# USB.net
KiCad netlist of a schematic drawn in Altium Designer
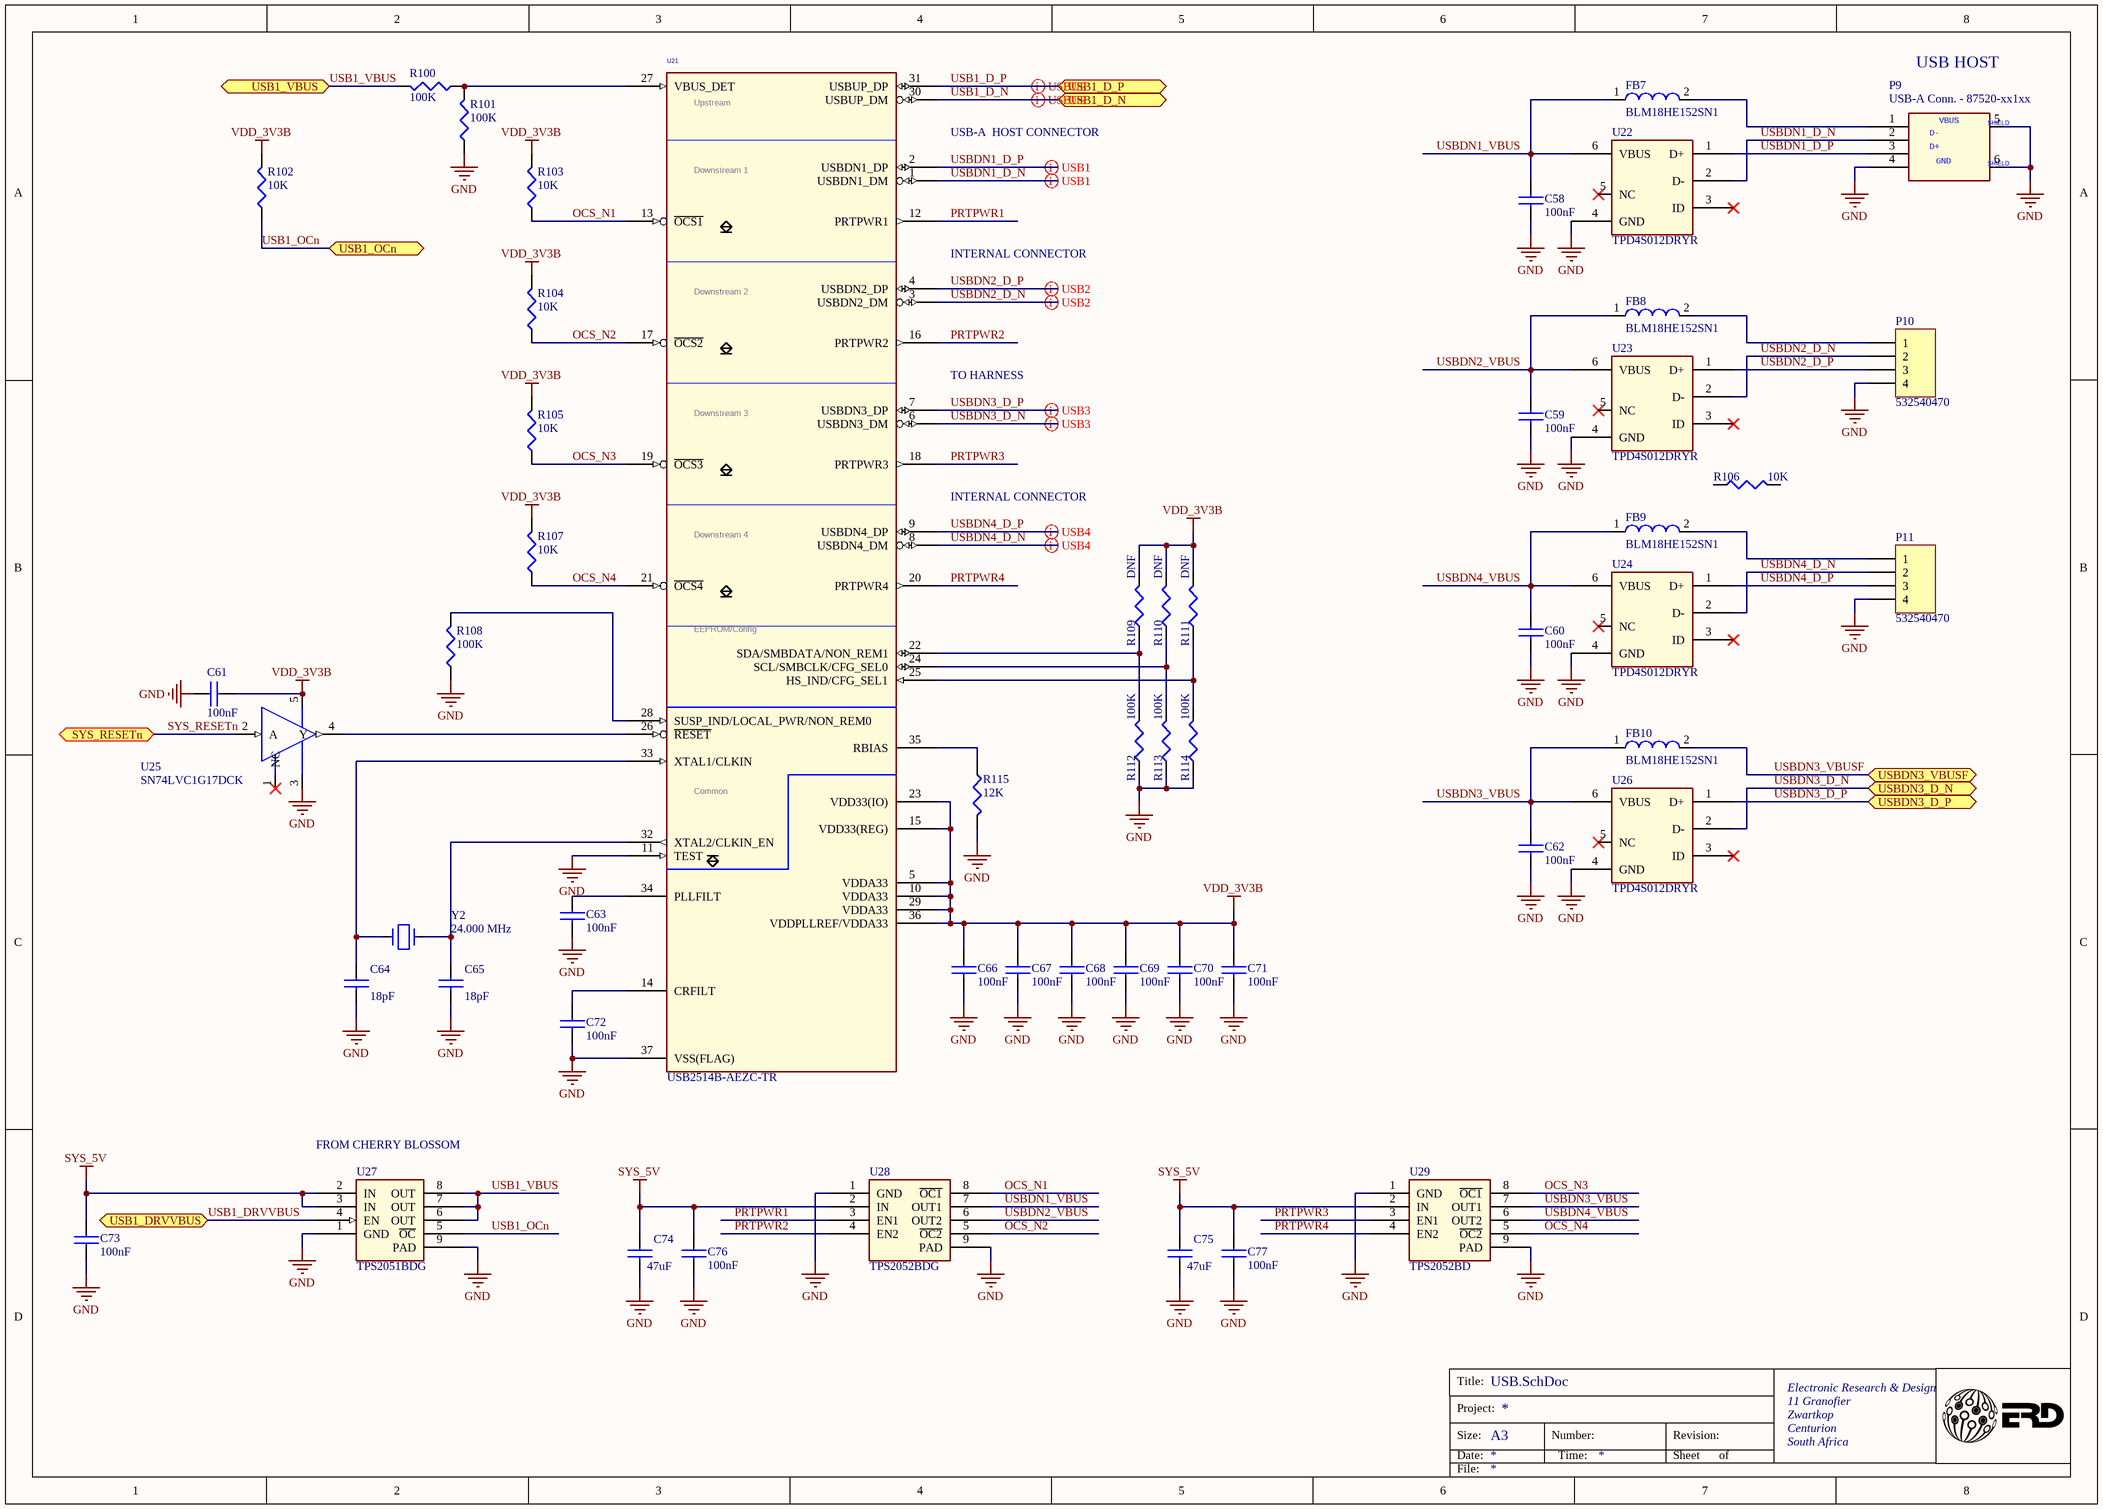
[diagram p0: USB.SchDoc]

(export (version "E")
  (design (tool "Eeschema 10.0.6"))
  (components
    (comp (ref "C58")
      (value "100nF")
      (footprint "CC0402")
      (description "CAP CER 0.1UF 50V 10% X7R 0402")
      (fields (field (name "MANUFACTURER") "Murata") (field (name "PARTNUMBER") "GCM155R71H104KE02D"))
      (libsource (lib "ERD TiAm") (part "CAP CER 0.1UF 10V 10% X5R 0402"))
    )
    (comp (ref "C59")
      (value "100nF")
      (footprint "CC0402")
      (description "CAP CER 0.1UF 50V 10% X7R 0402")
      (fields (field (name "MANUFACTURER") "Murata") (field (name "PARTNUMBER") "GCM155R71H104KE02D"))
      (libsource (lib "ERD TiAm") (part "CAP CER 0.1UF 10V 10% X5R 0402"))
    )
    (comp (ref "C60")
      (value "100nF")
      (footprint "CC0402")
      (description "CAP CER 0.1UF 50V 10% X7R 0402")
      (fields (field (name "MANUFACTURER") "Murata") (field (name "PARTNUMBER") "GCM155R71H104KE02D"))
      (libsource (lib "ERD TiAm") (part "CAP CER 0.1UF 10V 10% X5R 0402"))
    )
    (comp (ref "C61")
      (value "100nF")
      (footprint "CC0402")
      (description "CAP CER 0.1UF 50V 10% X7R 0402")
      (fields (field (name "MANUFACTURER") "Murata") (field (name "PARTNUMBER") "GCM155R71H104KE02D"))
      (libsource (lib "ERD TiAm") (part "CAP CER 0.1UF 10V 10% X5R 0402"))
    )
    (comp (ref "C62")
      (value "100nF")
      (footprint "CC0402")
      (description "CAP CER 0.1UF 50V 10% X7R 0402")
      (fields (field (name "MANUFACTURER") "Murata") (field (name "PARTNUMBER") "GCM155R71H104KE02D"))
      (libsource (lib "ERD TiAm") (part "CAP CER 0.1UF 10V 10% X5R 0402"))
    )
    (comp (ref "C63")
      (value "100nF")
      (footprint "CC0402")
      (description "CAP CER 0.1UF 50V 10% X7R 0402")
      (fields (field (name "MANUFACTURER") "Murata") (field (name "PARTNUMBER") "GCM155R71H104KE02D"))
      (libsource (lib "ERD TiAm") (part "CAP CER 0.1UF 10V 10% X5R 0402"))
    )
    (comp (ref "C64")
      (value "18pF")
      (footprint "CC0402")
      (description "CAP CER 18pF 50V 5% C0G 0402")
      (fields (field (name "MANUFACTURER") "AVX") (field (name "PARTNUMBER") "GJM1555C1H180FB01D"))
      (libsource (lib "ERD TiAm") (part "CAP CER 2.2UF 6.3V 10% X5R 0402"))
    )
    (comp (ref "C65")
      (value "18pF")
      (footprint "CC0402")
      (description "CAP CER 18pF 50V 5% C0G 0402")
      (fields (field (name "MANUFACTURER") "AVX") (field (name "PARTNUMBER") "GJM1555C1H180FB01D"))
      (libsource (lib "ERD TiAm") (part "CAP CER 2.2UF 6.3V 10% X5R 0402"))
    )
    (comp (ref "C66")
      (value "100nF")
      (footprint "CC0402")
      (description "CAP CER 0.1UF 50V 10% X7R 0402")
      (fields (field (name "MANUFACTURER") "Murata") (field (name "PARTNUMBER") "GCM155R71H104KE02D"))
      (libsource (lib "ERD TiAm") (part "CAP CER 0.1UF 10V 10% X5R 0402"))
    )
    (comp (ref "C67")
      (value "100nF")
      (footprint "CC0402")
      (description "CAP CER 0.1UF 50V 10% X7R 0402")
      (fields (field (name "MANUFACTURER") "Murata") (field (name "PARTNUMBER") "GCM155R71H104KE02D"))
      (libsource (lib "ERD TiAm") (part "CAP CER 0.1UF 10V 10% X5R 0402"))
    )
    (comp (ref "C68")
      (value "100nF")
      (footprint "CC0402")
      (description "CAP CER 0.1UF 50V 10% X7R 0402")
      (fields (field (name "MANUFACTURER") "Murata") (field (name "PARTNUMBER") "GCM155R71H104KE02D"))
      (libsource (lib "ERD TiAm") (part "CAP CER 0.1UF 10V 10% X5R 0402"))
    )
    (comp (ref "C69")
      (value "100nF")
      (footprint "CC0402")
      (description "CAP CER 0.1UF 50V 10% X7R 0402")
      (fields (field (name "MANUFACTURER") "Murata") (field (name "PARTNUMBER") "GCM155R71H104KE02D"))
      (libsource (lib "ERD TiAm") (part "CAP CER 0.1UF 10V 10% X5R 0402"))
    )
    (comp (ref "C70")
      (value "100nF")
      (footprint "CC0402")
      (description "CAP CER 0.1UF 50V 10% X7R 0402")
      (fields (field (name "MANUFACTURER") "Murata") (field (name "PARTNUMBER") "GCM155R71H104KE02D"))
      (libsource (lib "ERD TiAm") (part "CAP CER 0.1UF 10V 10% X5R 0402"))
    )
    (comp (ref "C71")
      (value "100nF")
      (footprint "CC0402")
      (description "CAP CER 0.1UF 50V 10% X7R 0402")
      (fields (field (name "MANUFACTURER") "Murata") (field (name "PARTNUMBER") "GCM155R71H104KE02D"))
      (libsource (lib "ERD TiAm") (part "CAP CER 0.1UF 10V 10% X5R 0402"))
    )
    (comp (ref "C72")
      (value "100nF")
      (footprint "CC0402")
      (description "CAP CER 0.1UF 50V 10% X7R 0402")
      (fields (field (name "MANUFACTURER") "Murata") (field (name "PARTNUMBER") "GCM155R71H104KE02D"))
      (libsource (lib "ERD TiAm") (part "CAP CER 0.1UF 10V 10% X5R 0402"))
    )
    (comp (ref "C73")
      (value "100nF")
      (footprint "CC0402")
      (description "CAP CER 0.1UF 50V 10% X7R 0402")
      (fields (field (name "MANUFACTURER") "Murata") (field (name "PARTNUMBER") "GCM155R71H104KE02D"))
      (libsource (lib "ERD TiAm") (part "CAP CER 0.1UF 10V 10% X5R 0402"))
    )
    (comp (ref "C74")
      (value "47uF")
      (footprint "RC1206")
      (description "CAP CER 47UF 25V 20% X5R 1206")
      (fields (field (name "MANUFACTURER") "Murata") (field (name "PART NUMBER") "C3216X5R1E476M160AC"))
      (libsource (lib "ERD TiAm") (part "CAP CER 0.1UF 10V 10% X5R 0402"))
    )
    (comp (ref "C75")
      (value "47uF")
      (footprint "RC1206")
      (description "CAP CER 47UF 25V 20% X5R 1206")
      (fields (field (name "MANUFACTURER") "Murata") (field (name "PART NUMBER") "C3216X5R1E476M160AC"))
      (libsource (lib "ERD TiAm") (part "CAP CER 0.1UF 10V 10% X5R 0402"))
    )
    (comp (ref "C76")
      (value "100nF")
      (footprint "CC0402")
      (description "CAP CER 0.1UF 50V 10% X7R 0402")
      (fields (field (name "MANUFACTURER") "Murata") (field (name "PARTNUMBER") "GCM155R71H104KE02D"))
      (libsource (lib "ERD TiAm") (part "CAP CER 0.1UF 10V 10% X5R 0402"))
    )
    (comp (ref "C77")
      (value "100nF")
      (footprint "CC0402")
      (description "CAP CER 0.1UF 50V 10% X7R 0402")
      (fields (field (name "MANUFACTURER") "Murata") (field (name "PARTNUMBER") "GCM155R71H104KE02D"))
      (libsource (lib "ERD TiAm") (part "CAP CER 0.1UF 10V 10% X5R 0402"))
    )
    (comp (ref "FB7")
      (value "BLM18HE152SN1")
      (footprint "LC0603")
      (description "FERRITE, 500mA, 500mOHM, 0603")
      (libsource (lib "BEAGLEBONEBLACK_REV A5B") (part "FER_180_200_0"))
    )
    (comp (ref "FB8")
      (value "BLM18HE152SN1")
      (footprint "LC0603")
      (description "FERRITE, 500mA, 500mOHM, 0603")
      (libsource (lib "BEAGLEBONEBLACK_REV A5B") (part "FER_180_200_0"))
    )
    (comp (ref "FB9")
      (value "BLM18HE152SN1")
      (footprint "LC0603")
      (description "FERRITE, 500mA, 500mOHM, 0603")
      (libsource (lib "BEAGLEBONEBLACK_REV A5B") (part "FER_180_200_0"))
    )
    (comp (ref "FB10")
      (value "BLM18HE152SN1")
      (footprint "LC0603")
      (description "FERRITE, 500mA, 500mOHM, 0603")
      (libsource (lib "BEAGLEBONEBLACK_REV A5B") (part "FER_180_200_0"))
    )
    (comp (ref "P9")
      (value "USB-A Conn. - 87520-xx1xx")
      (description "CONN RCPT USB TYPE A R/A PCB")
      (fields (field (name "MANUFACTURER") "FCI") (field (name "MANUFACTURER PART NUMBER") "87520-0010BLF"))
      (libsource (lib "BEAGLEBONEBLACK_REV A5B") (part "CONN_54819-0578_2"))
    )
    (comp (ref "P10")
      (value "532540470")
      (footprint "HDR1X4")
      (description "Header, RA, 4-circuit, 2mm pitch, TH")
      (fields (field (name "MANUFACTURER") "Molex"))
      (libsource (lib "Miscellaneous Connectors") (part "Header 4"))
    )
    (comp (ref "P11")
      (value "532540470")
      (footprint "HDR1X4")
      (description "Header, RA, 4-circuit, 2mm pitch, TH")
      (fields (field (name "MANUFACTURER") "Molex"))
      (libsource (lib "Miscellaneous Connectors") (part "Header 4"))
    )
    (comp (ref "R100")
      (value "100K")
      (footprint "RC0402")
      (description "RES, 100K OHM, 1/16W, 1%, 0402")
      (fields (field (name "MANUFACTURER") "Yageo") (field (name "PART NUMBER") "RC0402FR-07100KL"))
      (libsource (lib "ERD TiAm") (part "RES_10K_1/16W_1%_0402"))
    )
    (comp (ref "R101")
      (value "100K")
      (footprint "RC0402")
      (description "RES, 100K OHM, 1/16W, 1%, 0402")
      (fields (field (name "MANUFACTURER") "Yageo") (field (name "PART NUMBER") "RC0402FR-07100KL"))
      (libsource (lib "ERD TiAm") (part "RES_10K_1/16W_1%_0402"))
    )
    (comp (ref "R102")
      (value "10K")
      (footprint "RC0402")
      (description "RES, 10K OHM, 1/16W, 1%, 0402")
      (fields (field (name "MANUFACTURER") "Yageo") (field (name "PART NUMBER") "RC0402FR-0710KL"))
      (libsource (lib "ERD TiAm") (part "RES_10K_1/16W_1%_0402"))
    )
    (comp (ref "R103")
      (value "10K")
      (footprint "RC0402")
      (description "RES, 10K OHM, 1/16W, 1%, 0402")
      (fields (field (name "MANUFACTURER") "Yageo") (field (name "PART NUMBER") "RC0402FR-0710KL"))
      (libsource (lib "ERD TiAm") (part "RES_10K_1/16W_1%_0402"))
    )
    (comp (ref "R104")
      (value "10K")
      (footprint "RC0402")
      (description "RES, 10K OHM, 1/16W, 1%, 0402")
      (fields (field (name "MANUFACTURER") "Yageo") (field (name "PART NUMBER") "RC0402FR-0710KL"))
      (libsource (lib "ERD TiAm") (part "RES_10K_1/16W_1%_0402"))
    )
    (comp (ref "R105")
      (value "10K")
      (footprint "RC0402")
      (description "RES, 10K OHM, 1/16W, 1%, 0402")
      (fields (field (name "MANUFACTURER") "Yageo") (field (name "PART NUMBER") "RC0402FR-0710KL"))
      (libsource (lib "ERD TiAm") (part "RES_10K_1/16W_1%_0402"))
    )
    (comp (ref "R106")
      (value "10K")
      (footprint "RC0402")
      (description "RES, 10K OHM, 1/16W, 1%, 0402")
      (fields (field (name "MANUFACTURER") "Yageo") (field (name "PART NUMBER") "RC0402FR-0710KL"))
      (libsource (lib "ERD TiAm") (part "RES_10K_1/16W_1%_0402"))
    )
    (comp (ref "R107")
      (value "10K")
      (footprint "RC0402")
      (description "RES, 10K OHM, 1/16W, 1%, 0402")
      (fields (field (name "MANUFACTURER") "Yageo") (field (name "PART NUMBER") "RC0402FR-0710KL"))
      (libsource (lib "ERD TiAm") (part "RES_10K_1/16W_1%_0402"))
    )
    (comp (ref "R108")
      (value "100K")
      (footprint "RC0402")
      (description "RES, 100K OHM, 1/16W, 1%, 0402")
      (fields (field (name "MANUFACTURER") "Yageo") (field (name "PART NUMBER") "RC0402FR-07100KL"))
      (libsource (lib "ERD TiAm") (part "RES_10K_1/16W_1%_0402"))
    )
    (comp (ref "R109")
      (value "DNF")
      (footprint "RC0402")
      (description "RES, 10K OHM, 1/16W, 1%, 0402")
      (fields (field (name "MANUFACTURER") "Yageo") (field (name "PART NUMBER") "RC0402FR-0710KL"))
      (libsource (lib "ERD TiAm") (part "RES_10K_1/16W_1%_0402"))
    )
    (comp (ref "R110")
      (value "DNF")
      (footprint "RC0402")
      (description "RES, 10K OHM, 1/16W, 1%, 0402")
      (fields (field (name "MANUFACTURER") "Yageo") (field (name "PART NUMBER") "RC0402FR-0710KL"))
      (libsource (lib "ERD TiAm") (part "RES_10K_1/16W_1%_0402"))
    )
    (comp (ref "R111")
      (value "DNF")
      (footprint "RC0402")
      (description "RES, 10K OHM, 1/16W, 1%, 0402")
      (fields (field (name "MANUFACTURER") "Yageo") (field (name "PART NUMBER") "RC0402FR-0710KL"))
      (libsource (lib "ERD TiAm") (part "RES_10K_1/16W_1%_0402"))
    )
    (comp (ref "R112")
      (value "100K")
      (footprint "RC0402")
      (description "RES, 100K OHM, 1/16W, 1%, 0402")
      (fields (field (name "MANUFACTURER") "Yageo") (field (name "PART NUMBER") "RC0402FR-07100KL"))
      (libsource (lib "ERD TiAm") (part "RES_10K_1/16W_1%_0402"))
    )
    (comp (ref "R113")
      (value "100K")
      (footprint "RC0402")
      (description "RES, 100K OHM, 1/16W, 1%, 0402")
      (fields (field (name "MANUFACTURER") "Yageo") (field (name "PART NUMBER") "RC0402FR-07100KL"))
      (libsource (lib "ERD TiAm") (part "RES_10K_1/16W_1%_0402"))
    )
    (comp (ref "R114")
      (value "100K")
      (footprint "RC0402")
      (description "RES, 100K OHM, 1/16W, 1%, 0402")
      (fields (field (name "MANUFACTURER") "Yageo") (field (name "PART NUMBER") "RC0402FR-07100KL"))
      (libsource (lib "ERD TiAm") (part "RES_10K_1/16W_1%_0402"))
    )
    (comp (ref "R115")
      (value "12K")
      (footprint "RC0402")
      (description "RES, 12K OHM, 1/16W, 1%, 0402")
      (fields (field (name "MANUFACTURER") "Yageo") (field (name "PART NUMBER") "RC0402FR-0712KL"))
      (libsource (lib "ERD TiAm") (part "RES_10K_1/16W_1%_0402"))
    )
    (comp (ref "U21")
      (value "USB2514B-AEZC-TR")
      (footprint "SQFN-36")
      (description "IC, USB2514B, 4 Port USB 2.0 Hub w/ Battery Chg, QFN36")
      (libsource (lib "ERD TiAm") (part "USB2514B_QFN36_MIN"))
    )
    (comp (ref "U22")
      (value "TPD4S012DRYR")
      (footprint "U_6_DRY")
      (description "ESD 4channel USB Interface")
      (fields (field (name "MANUFACTURER") "Texas Instruments"))
      (libsource (lib "ERD TiAm") (part "PROT_TPD4S012"))
    )
    (comp (ref "U23")
      (value "TPD4S012DRYR")
      (footprint "U_6_DRY")
      (description "ESD 4channel USB Interface")
      (fields (field (name "MANUFACTURER") "Texas Instruments"))
      (libsource (lib "ERD TiAm") (part "PROT_TPD4S012"))
    )
    (comp (ref "U24")
      (value "TPD4S012DRYR")
      (footprint "U_6_DRY")
      (description "ESD 4channel USB Interface")
      (fields (field (name "MANUFACTURER") "Texas Instruments"))
      (libsource (lib "ERD TiAm") (part "PROT_TPD4S012"))
    )
    (comp (ref "U25")
      (value "SN74LVC1G17DCK")
      (footprint "DCK5_2P15X1P4")
      (description "IC Buffer SINGLE 1INPUT SC70-5")
      (fields (field (name "MANUFACTURER") "Texas Instruments"))
      (libsource (lib "ERD TiAm") (part "SN74LVC1G17DCK"))
    )
    (comp (ref "U26")
      (value "TPD4S012DRYR")
      (footprint "U_6_DRY")
      (description "ESD 4channel USB Interface")
      (fields (field (name "MANUFACTURER") "Texas Instruments"))
      (libsource (lib "ERD TiAm") (part "PROT_TPD4S012"))
    )
    (comp (ref "U27")
      (value "TPS2051BDG")
      (description "IC 1.5A PWR DIST SWITCH 8-MSOP")
      (fields (field (name "MANUFACTURER") "Texas Instruments"))
      (libsource (lib "BEAGLEBONEBLACK_REV A5B") (part "TPS2061_0"))
    )
    (comp (ref "U28")
      (value "TPS2052BDG")
      (description "IC 0.7A PWR DIST SWITCH 8-MSOP")
      (fields (field (name "ALTPARTNUMBER") "MP6231DH"))
      (libsource (lib "BaseBoard") (part "TPS2052"))
    )
    (comp (ref "U29")
      (value "TPS2052BD")
      (description "IC 0.7A PWR DIST SWITCH 8-MSOP")
      (fields (field (name "ALTPARTNUMBER") "MP6231DH"))
      (libsource (lib "BaseBoard") (part "TPS2052"))
    )
    (comp (ref "Y2")
      (value "24.000 MHz")
      (footprint "XTAL150SMD_125X196")
      (description "Crystal, 24 MHz, 20ppm, 2-SMD")
      (fields (field (name "PARTNUMBER") "ABM3-24.000MHZ-B2-T"))
      (libsource (lib "altium-import") (part "root_0_CRYSTAL - 2 PIN_"))
    )
  )
  (nets
    (net (code "1") (name "/OCS_N1") (class "Default")
      (node (ref "R103") (pin "1") (pinfunction "1_1") (pintype "passive"))
      (node (ref "U21") (pin "13") (pinfunction "~{OCS1}_13") (pintype "input"))
      (node (ref "U28") (pin "8") (pinfunction "~{OC1}_8") (pintype "power_in"))
    )
    (net (code "2") (name "/OCS_N2") (class "Default")
      (node (ref "R104") (pin "1") (pinfunction "1_1") (pintype "passive"))
      (node (ref "U21") (pin "17") (pinfunction "~{OCS2}_17") (pintype "input"))
      (node (ref "U28") (pin "5") (pinfunction "~{OC2}_5") (pintype "passive"))
    )
    (net (code "3") (name "/OCS_N3") (class "Default")
      (node (ref "R105") (pin "1") (pinfunction "1_1") (pintype "passive"))
      (node (ref "U21") (pin "19") (pinfunction "~{OCS3}_19") (pintype "input"))
      (node (ref "U29") (pin "8") (pinfunction "~{OC1}_8") (pintype "power_in"))
    )
    (net (code "4") (name "/OCS_N4") (class "Default")
      (node (ref "R107") (pin "1") (pinfunction "1_1") (pintype "passive"))
      (node (ref "U21") (pin "21") (pinfunction "~{OCS4}_21") (pintype "input"))
      (node (ref "U29") (pin "5") (pinfunction "~{OC2}_5") (pintype "passive"))
    )
    (net (code "5") (name "/PRTPWR1") (class "Default")
      (node (ref "U21") (pin "12") (pinfunction "PRTPWR1_12") (pintype "output"))
      (node (ref "U28") (pin "3") (pinfunction "EN1_3") (pintype "passive"))
    )
    (net (code "6") (name "/PRTPWR2") (class "Default")
      (node (ref "U21") (pin "16") (pinfunction "PRTPWR2_16") (pintype "output"))
      (node (ref "U28") (pin "4") (pinfunction "EN2_4") (pintype "passive"))
    )
    (net (code "7") (name "/PRTPWR3") (class "Default")
      (node (ref "U21") (pin "18") (pinfunction "PRTPWR3_18") (pintype "output"))
      (node (ref "U29") (pin "3") (pinfunction "EN1_3") (pintype "passive"))
    )
    (net (code "8") (name "/PRTPWR4") (class "Default")
      (node (ref "U21") (pin "20") (pinfunction "PRTPWR4_20") (pintype "output"))
      (node (ref "U29") (pin "4") (pinfunction "EN2_4") (pintype "passive"))
    )
    (net (code "9") (name "/SYS_RESETn") (class "Default")
      (node (ref "U25") (pin "2") (pinfunction "A_2") (pintype "input"))
    )
    (net (code "10") (name "/USB1_DRVVBUS") (class "Default")
      (node (ref "U27") (pin "4") (pinfunction "EN_4") (pintype "input"))
    )
    (net (code "11") (name "/USB1_D_N") (class "Default")
      (node (ref "U21") (pin "30") (pinfunction "USBUP_DM_30") (pintype "bidirectional"))
    )
    (net (code "12") (name "/USB1_D_P") (class "Default")
      (node (ref "U21") (pin "31") (pinfunction "USBUP_DP_31") (pintype "bidirectional"))
    )
    (net (code "13") (name "/USB1_OCn") (class "Default")
      (node (ref "R102") (pin "1") (pinfunction "1_1") (pintype "passive"))
      (node (ref "U27") (pin "5") (pinfunction "~{OC}_5") (pintype "passive"))
    )
    (net (code "14") (name "/USB1_VBUS") (class "Default")
      (node (ref "R100") (pin "2") (pinfunction "2_2") (pintype "passive"))
      (node (ref "U27") (pin "6") (pinfunction "OUT_6") (pintype "power_in"))
      (node (ref "U27") (pin "7") (pinfunction "OUT_7") (pintype "power_in"))
      (node (ref "U27") (pin "8") (pinfunction "OUT_8") (pintype "power_in"))
    )
    (net (code "15") (name "/USBDN1_D_N") (class "Default")
      (node (ref "P9") (pin "2") (pinfunction "P2_2") (pintype "passive"))
      (node (ref "U21") (pin "1") (pinfunction "USBDN1_DM_1") (pintype "bidirectional"))
      (node (ref "U22") (pin "2") (pinfunction "D-_2") (pintype "passive"))
    )
    (net (code "16") (name "/USBDN1_D_P") (class "Default")
      (node (ref "P9") (pin "3") (pinfunction "P3_3") (pintype "passive"))
      (node (ref "U21") (pin "2") (pinfunction "USBDN1_DP_2") (pintype "bidirectional"))
      (node (ref "U22") (pin "1") (pinfunction "D+_1") (pintype "passive"))
    )
    (net (code "17") (name "/USBDN1_VBUS") (class "Default")
      (node (ref "C58") (pin "1") (pinfunction "1_1") (pintype "passive"))
      (node (ref "FB7") (pin "1") (pinfunction "1_1") (pintype "passive"))
      (node (ref "U22") (pin "6") (pinfunction "VBUS_6") (pintype "power_in"))
      (node (ref "U28") (pin "7") (pinfunction "OUT1_7") (pintype "power_in"))
    )
    (net (code "18") (name "/USBDN2_D_N") (class "Default")
      (node (ref "P10") (pin "2") (pinfunction "2_2") (pintype "passive"))
      (node (ref "U21") (pin "3") (pinfunction "USBDN2_DM_3") (pintype "bidirectional"))
      (node (ref "U23") (pin "2") (pinfunction "D-_2") (pintype "passive"))
    )
    (net (code "19") (name "/USBDN2_D_P") (class "Default")
      (node (ref "P10") (pin "3") (pinfunction "3_3") (pintype "passive"))
      (node (ref "U21") (pin "4") (pinfunction "USBDN2_DP_4") (pintype "bidirectional"))
      (node (ref "U23") (pin "1") (pinfunction "D+_1") (pintype "passive"))
    )
    (net (code "20") (name "/USBDN2_VBUS") (class "Default")
      (node (ref "C59") (pin "1") (pinfunction "1_1") (pintype "passive"))
      (node (ref "FB8") (pin "1") (pinfunction "1_1") (pintype "passive"))
      (node (ref "U23") (pin "6") (pinfunction "VBUS_6") (pintype "power_in"))
      (node (ref "U28") (pin "6") (pinfunction "OUT2_6") (pintype "power_in"))
    )
    (net (code "21") (name "/USBDN3_D_N") (class "Default")
      (node (ref "U21") (pin "6") (pinfunction "USBDN3_DM_6") (pintype "bidirectional"))
      (node (ref "U26") (pin "2") (pinfunction "D-_2") (pintype "passive"))
    )
    (net (code "22") (name "/USBDN3_D_P") (class "Default")
      (node (ref "U21") (pin "7") (pinfunction "USBDN3_DP_7") (pintype "bidirectional"))
      (node (ref "U26") (pin "1") (pinfunction "D+_1") (pintype "passive"))
    )
    (net (code "23") (name "/USBDN3_VBUS") (class "Default")
      (node (ref "C62") (pin "1") (pinfunction "1_1") (pintype "passive"))
      (node (ref "FB10") (pin "1") (pinfunction "1_1") (pintype "passive"))
      (node (ref "U26") (pin "6") (pinfunction "VBUS_6") (pintype "power_in"))
      (node (ref "U29") (pin "7") (pinfunction "OUT1_7") (pintype "power_in"))
    )
    (net (code "24") (name "/USBDN3_VBUSF") (class "Default")
      (node (ref "FB10") (pin "2") (pinfunction "2_2") (pintype "passive"))
    )
    (net (code "25") (name "/USBDN4_D_N") (class "Default")
      (node (ref "P11") (pin "2") (pinfunction "2_2") (pintype "passive"))
      (node (ref "U21") (pin "8") (pinfunction "USBDN4_DM_8") (pintype "bidirectional"))
      (node (ref "U24") (pin "2") (pinfunction "D-_2") (pintype "passive"))
    )
    (net (code "26") (name "/USBDN4_D_P") (class "Default")
      (node (ref "P11") (pin "3") (pinfunction "3_3") (pintype "passive"))
      (node (ref "U21") (pin "9") (pinfunction "USBDN4_DP_9") (pintype "bidirectional"))
      (node (ref "U24") (pin "1") (pinfunction "D+_1") (pintype "passive"))
    )
    (net (code "27") (name "/USBDN4_VBUS") (class "Default")
      (node (ref "C60") (pin "1") (pinfunction "1_1") (pintype "passive"))
      (node (ref "FB9") (pin "1") (pinfunction "1_1") (pintype "passive"))
      (node (ref "U24") (pin "6") (pinfunction "VBUS_6") (pintype "power_in"))
      (node (ref "U29") (pin "6") (pinfunction "OUT2_6") (pintype "power_in"))
    )
    (net (code "28") (name "GND") (class "Default")
      (node (ref "C58") (pin "2") (pinfunction "2_2") (pintype "passive"))
      (node (ref "C59") (pin "2") (pinfunction "2_2") (pintype "passive"))
      (node (ref "C60") (pin "2") (pinfunction "2_2") (pintype "passive"))
      (node (ref "C61") (pin "1") (pinfunction "1_1") (pintype "passive"))
      (node (ref "C62") (pin "2") (pinfunction "2_2") (pintype "passive"))
      (node (ref "C63") (pin "2") (pinfunction "2_2") (pintype "passive"))
      (node (ref "C64") (pin "2") (pinfunction "2_2") (pintype "passive"))
      (node (ref "C65") (pin "2") (pinfunction "2_2") (pintype "passive"))
      (node (ref "C66") (pin "2") (pinfunction "2_2") (pintype "passive"))
      (node (ref "C67") (pin "2") (pinfunction "2_2") (pintype "passive"))
      (node (ref "C68") (pin "2") (pinfunction "2_2") (pintype "passive"))
      (node (ref "C69") (pin "2") (pinfunction "2_2") (pintype "passive"))
      (node (ref "C70") (pin "2") (pinfunction "2_2") (pintype "passive"))
      (node (ref "C71") (pin "2") (pinfunction "2_2") (pintype "passive"))
      (node (ref "C72") (pin "2") (pinfunction "2_2") (pintype "passive"))
      (node (ref "C73") (pin "2") (pinfunction "2_2") (pintype "passive"))
      (node (ref "C74") (pin "2") (pinfunction "2_2") (pintype "passive"))
      (node (ref "C75") (pin "2") (pinfunction "2_2") (pintype "passive"))
      (node (ref "C76") (pin "2") (pinfunction "2_2") (pintype "passive"))
      (node (ref "C77") (pin "2") (pinfunction "2_2") (pintype "passive"))
      (node (ref "P10") (pin "4") (pinfunction "4_4") (pintype "passive"))
      (node (ref "P11") (pin "4") (pinfunction "4_4") (pintype "passive"))
      (node (ref "P9") (pin "4") (pinfunction "P4_4") (pintype "passive"))
      (node (ref "P9") (pin "5") (pinfunction "SHELD1_5") (pintype "passive"))
      (node (ref "P9") (pin "6") (pinfunction "PAD4_6") (pintype "passive"))
      (node (ref "R101") (pin "1") (pinfunction "1_1") (pintype "passive"))
      (node (ref "R108") (pin "1") (pinfunction "1_1") (pintype "passive"))
      (node (ref "R112") (pin "1") (pinfunction "1_1") (pintype "passive"))
      (node (ref "R113") (pin "1") (pinfunction "1_1") (pintype "passive"))
      (node (ref "R114") (pin "1") (pinfunction "1_1") (pintype "passive"))
      (node (ref "R115") (pin "2") (pinfunction "2_2") (pintype "passive"))
      (node (ref "U21") (pin "11") (pinfunction "TEST_11") (pintype "input"))
      (node (ref "U21") (pin "37") (pinfunction "VSS(FLAG)_37") (pintype "power_in"))
      (node (ref "U22") (pin "4") (pinfunction "GND_4") (pintype "power_in"))
      (node (ref "U23") (pin "4") (pinfunction "GND_4") (pintype "power_in"))
      (node (ref "U24") (pin "4") (pinfunction "GND_4") (pintype "power_in"))
      (node (ref "U25") (pin "3") (pinfunction "GND_3") (pintype "power_in"))
      (node (ref "U26") (pin "4") (pinfunction "GND_4") (pintype "power_in"))
      (node (ref "U27") (pin "1") (pinfunction "GND_1") (pintype "power_in"))
      (node (ref "U27") (pin "9") (pinfunction "PAD_9") (pintype "passive"))
      (node (ref "U28") (pin "1") (pinfunction "GND_1") (pintype "power_in"))
      (node (ref "U28") (pin "9") (pinfunction "PAD_9") (pintype "passive"))
      (node (ref "U29") (pin "1") (pinfunction "GND_1") (pintype "power_in"))
      (node (ref "U29") (pin "9") (pinfunction "PAD_9") (pintype "passive"))
    )
    (net (code "29") (name "Net-(FB8-Pad2)") (class "Default")
      (node (ref "FB8") (pin "2") (pinfunction "2_2") (pintype "passive"))
      (node (ref "P10") (pin "1") (pinfunction "1_1") (pintype "passive"))
    )
    (net (code "30") (name "Net-(FB9-Pad2)") (class "Default")
      (node (ref "FB9") (pin "2") (pinfunction "2_2") (pintype "passive"))
      (node (ref "P11") (pin "1") (pinfunction "1_1") (pintype "passive"))
    )
    (net (code "31") (name "Net-(P9-P1)") (class "Default")
      (node (ref "FB7") (pin "2") (pinfunction "2_2") (pintype "passive"))
      (node (ref "P9") (pin "1") (pinfunction "P1_1") (pintype "passive"))
    )
    (net (code "32") (name "Net-(U21-CRFILT)") (class "Default")
      (node (ref "C72") (pin "1") (pinfunction "1_1") (pintype "passive"))
      (node (ref "U21") (pin "14") (pinfunction "CRFILT_14") (pintype "power_in"))
    )
    (net (code "33") (name "Net-(U21-HS_IND{slash}CFG_SEL1)") (class "Default")
      (node (ref "R111") (pin "1") (pinfunction "1_1") (pintype "passive"))
      (node (ref "R114") (pin "2") (pinfunction "2_2") (pintype "passive"))
      (node (ref "U21") (pin "25") (pinfunction "HS_IND/CFG_SEL1_25") (pintype "input"))
    )
    (net (code "34") (name "Net-(U21-PLLFILT)") (class "Default")
      (node (ref "C63") (pin "1") (pinfunction "1_1") (pintype "passive"))
      (node (ref "U21") (pin "34") (pinfunction "PLLFILT_34") (pintype "power_in"))
    )
    (net (code "35") (name "Net-(U21-RBIAS)") (class "Default")
      (node (ref "R115") (pin "1") (pinfunction "1_1") (pintype "passive"))
      (node (ref "U21") (pin "35") (pinfunction "RBIAS_35") (pintype "passive"))
    )
    (net (code "36") (name "Net-(U21-SCL{slash}SMBCLK{slash}CFG_SEL0)") (class "Default")
      (node (ref "R110") (pin "1") (pinfunction "1_1") (pintype "passive"))
      (node (ref "R113") (pin "2") (pinfunction "2_2") (pintype "passive"))
      (node (ref "U21") (pin "24") (pinfunction "SCL/SMBCLK/CFG_SEL0_24") (pintype "bidirectional"))
    )
    (net (code "37") (name "Net-(U21-SDA{slash}SMBDATA{slash}NON_REM1)") (class "Default")
      (node (ref "R109") (pin "1") (pinfunction "1_1") (pintype "passive"))
      (node (ref "R112") (pin "2") (pinfunction "2_2") (pintype "passive"))
      (node (ref "U21") (pin "22") (pinfunction "SDA/SMBDATA/NON_REM1_22") (pintype "bidirectional"))
    )
    (net (code "38") (name "Net-(U21-SUSP_IND{slash}LOCAL_PWR{slash}NON_REM0)") (class "Default")
      (node (ref "R108") (pin "2") (pinfunction "2_2") (pintype "passive"))
      (node (ref "U21") (pin "28") (pinfunction "SUSP_IND/LOCAL_PWR/NON_REM0_28") (pintype "input"))
    )
    (net (code "39") (name "Net-(U21-VBUS_DET)") (class "Default")
      (node (ref "R100") (pin "1") (pinfunction "1_1") (pintype "passive"))
      (node (ref "R101") (pin "2") (pinfunction "2_2") (pintype "passive"))
      (node (ref "U21") (pin "27") (pinfunction "VBUS_DET_27") (pintype "input"))
    )
    (net (code "40") (name "Net-(U21-XTAL1{slash}CLKIN)") (class "Default")
      (node (ref "C64") (pin "1") (pinfunction "1_1") (pintype "passive"))
      (node (ref "U21") (pin "33") (pinfunction "XTAL1/CLKIN_33") (pintype "input"))
      (node (ref "Y2") (pin "1") (pinfunction "1_1") (pintype "passive"))
    )
    (net (code "41") (name "Net-(U21-XTAL2{slash}CLKIN_EN)") (class "Default")
      (node (ref "C65") (pin "1") (pinfunction "1_1") (pintype "passive"))
      (node (ref "U21") (pin "32") (pinfunction "XTAL2/CLKIN_EN_32") (pintype "output"))
      (node (ref "Y2") (pin "2") (pinfunction "2_2") (pintype "passive"))
    )
    (net (code "42") (name "Net-(U21-~{RESET})") (class "Default")
      (node (ref "U21") (pin "26") (pinfunction "~{RESET}_26") (pintype "input"))
      (node (ref "U25") (pin "4") (pinfunction "Y_4") (pintype "output"))
    )
    (net (code "43") (name "SYS_5V") (class "Default")
      (node (ref "C73") (pin "1") (pinfunction "1_1") (pintype "passive"))
      (node (ref "C74") (pin "1") (pinfunction "1_1") (pintype "passive"))
      (node (ref "C75") (pin "1") (pinfunction "1_1") (pintype "passive"))
      (node (ref "C76") (pin "1") (pinfunction "1_1") (pintype "passive"))
      (node (ref "C77") (pin "1") (pinfunction "1_1") (pintype "passive"))
      (node (ref "U27") (pin "2") (pinfunction "IN_2") (pintype "power_in"))
      (node (ref "U27") (pin "3") (pinfunction "IN_3") (pintype "power_in"))
      (node (ref "U28") (pin "2") (pinfunction "IN_2") (pintype "power_in"))
      (node (ref "U29") (pin "2") (pinfunction "IN_2") (pintype "power_in"))
    )
    (net (code "44") (name "VDD_3V3B") (class "Default")
      (node (ref "C61") (pin "2") (pinfunction "2_2") (pintype "passive"))
      (node (ref "C66") (pin "1") (pinfunction "1_1") (pintype "passive"))
      (node (ref "C67") (pin "1") (pinfunction "1_1") (pintype "passive"))
      (node (ref "C68") (pin "1") (pinfunction "1_1") (pintype "passive"))
      (node (ref "C69") (pin "1") (pinfunction "1_1") (pintype "passive"))
      (node (ref "C70") (pin "1") (pinfunction "1_1") (pintype "passive"))
      (node (ref "C71") (pin "1") (pinfunction "1_1") (pintype "passive"))
      (node (ref "R102") (pin "2") (pinfunction "2_2") (pintype "passive"))
      (node (ref "R103") (pin "2") (pinfunction "2_2") (pintype "passive"))
      (node (ref "R104") (pin "2") (pinfunction "2_2") (pintype "passive"))
      (node (ref "R105") (pin "2") (pinfunction "2_2") (pintype "passive"))
      (node (ref "R107") (pin "2") (pinfunction "2_2") (pintype "passive"))
      (node (ref "R109") (pin "2") (pinfunction "2_2") (pintype "passive"))
      (node (ref "R110") (pin "2") (pinfunction "2_2") (pintype "passive"))
      (node (ref "R111") (pin "2") (pinfunction "2_2") (pintype "passive"))
      (node (ref "U21") (pin "10") (pinfunction "VDDA33_10") (pintype "power_in"))
      (node (ref "U21") (pin "15") (pinfunction "VDD33(REG)_15") (pintype "power_in"))
      (node (ref "U21") (pin "23") (pinfunction "VDD33(IO)_23") (pintype "power_in"))
      (node (ref "U21") (pin "29") (pinfunction "VDDA33_29") (pintype "power_in"))
      (node (ref "U21") (pin "36") (pinfunction "VDDPLLREF/VDDA33_36") (pintype "power_in"))
      (node (ref "U21") (pin "5") (pinfunction "VDDA33_5") (pintype "power_in"))
      (node (ref "U25") (pin "5") (pinfunction "VCC_5") (pintype "power_in"))
    )
    (net (code "45") (name "unconnected-(R106-Pad1)") (class "Default")
      (node (ref "R106") (pin "1") (pinfunction "1_1") (pintype "passive"))
    )
    (net (code "46") (name "unconnected-(R106-Pad2)") (class "Default")
      (node (ref "R106") (pin "2") (pinfunction "2_2") (pintype "passive"))
    )
    (net (code "47") (name "unconnected-(U22-ID-Pad3)") (class "Default")
      (node (ref "U22") (pin "3") (pinfunction "ID_3") (pintype "passive+no_connect"))
    )
    (net (code "48") (name "unconnected-(U22-NC-Pad5)") (class "Default")
      (node (ref "U22") (pin "5") (pinfunction "NC_5") (pintype "passive+no_connect"))
    )
    (net (code "49") (name "unconnected-(U23-ID-Pad3)") (class "Default")
      (node (ref "U23") (pin "3") (pinfunction "ID_3") (pintype "passive+no_connect"))
    )
    (net (code "50") (name "unconnected-(U23-NC-Pad5)") (class "Default")
      (node (ref "U23") (pin "5") (pinfunction "NC_5") (pintype "passive+no_connect"))
    )
    (net (code "51") (name "unconnected-(U24-ID-Pad3)") (class "Default")
      (node (ref "U24") (pin "3") (pinfunction "ID_3") (pintype "passive+no_connect"))
    )
    (net (code "52") (name "unconnected-(U24-NC-Pad5)") (class "Default")
      (node (ref "U24") (pin "5") (pinfunction "NC_5") (pintype "passive+no_connect"))
    )
    (net (code "53") (name "unconnected-(U25-NC-Pad1)") (class "Default")
      (node (ref "U25") (pin "1") (pinfunction "NC_1") (pintype "passive+no_connect"))
    )
    (net (code "54") (name "unconnected-(U26-ID-Pad3)") (class "Default")
      (node (ref "U26") (pin "3") (pinfunction "ID_3") (pintype "passive+no_connect"))
    )
    (net (code "55") (name "unconnected-(U26-NC-Pad5)") (class "Default")
      (node (ref "U26") (pin "5") (pinfunction "NC_5") (pintype "passive+no_connect"))
    )
  )
)
